# SPD_Programmer.net
KiCad netlist of a schematic drawn in Altium Designer
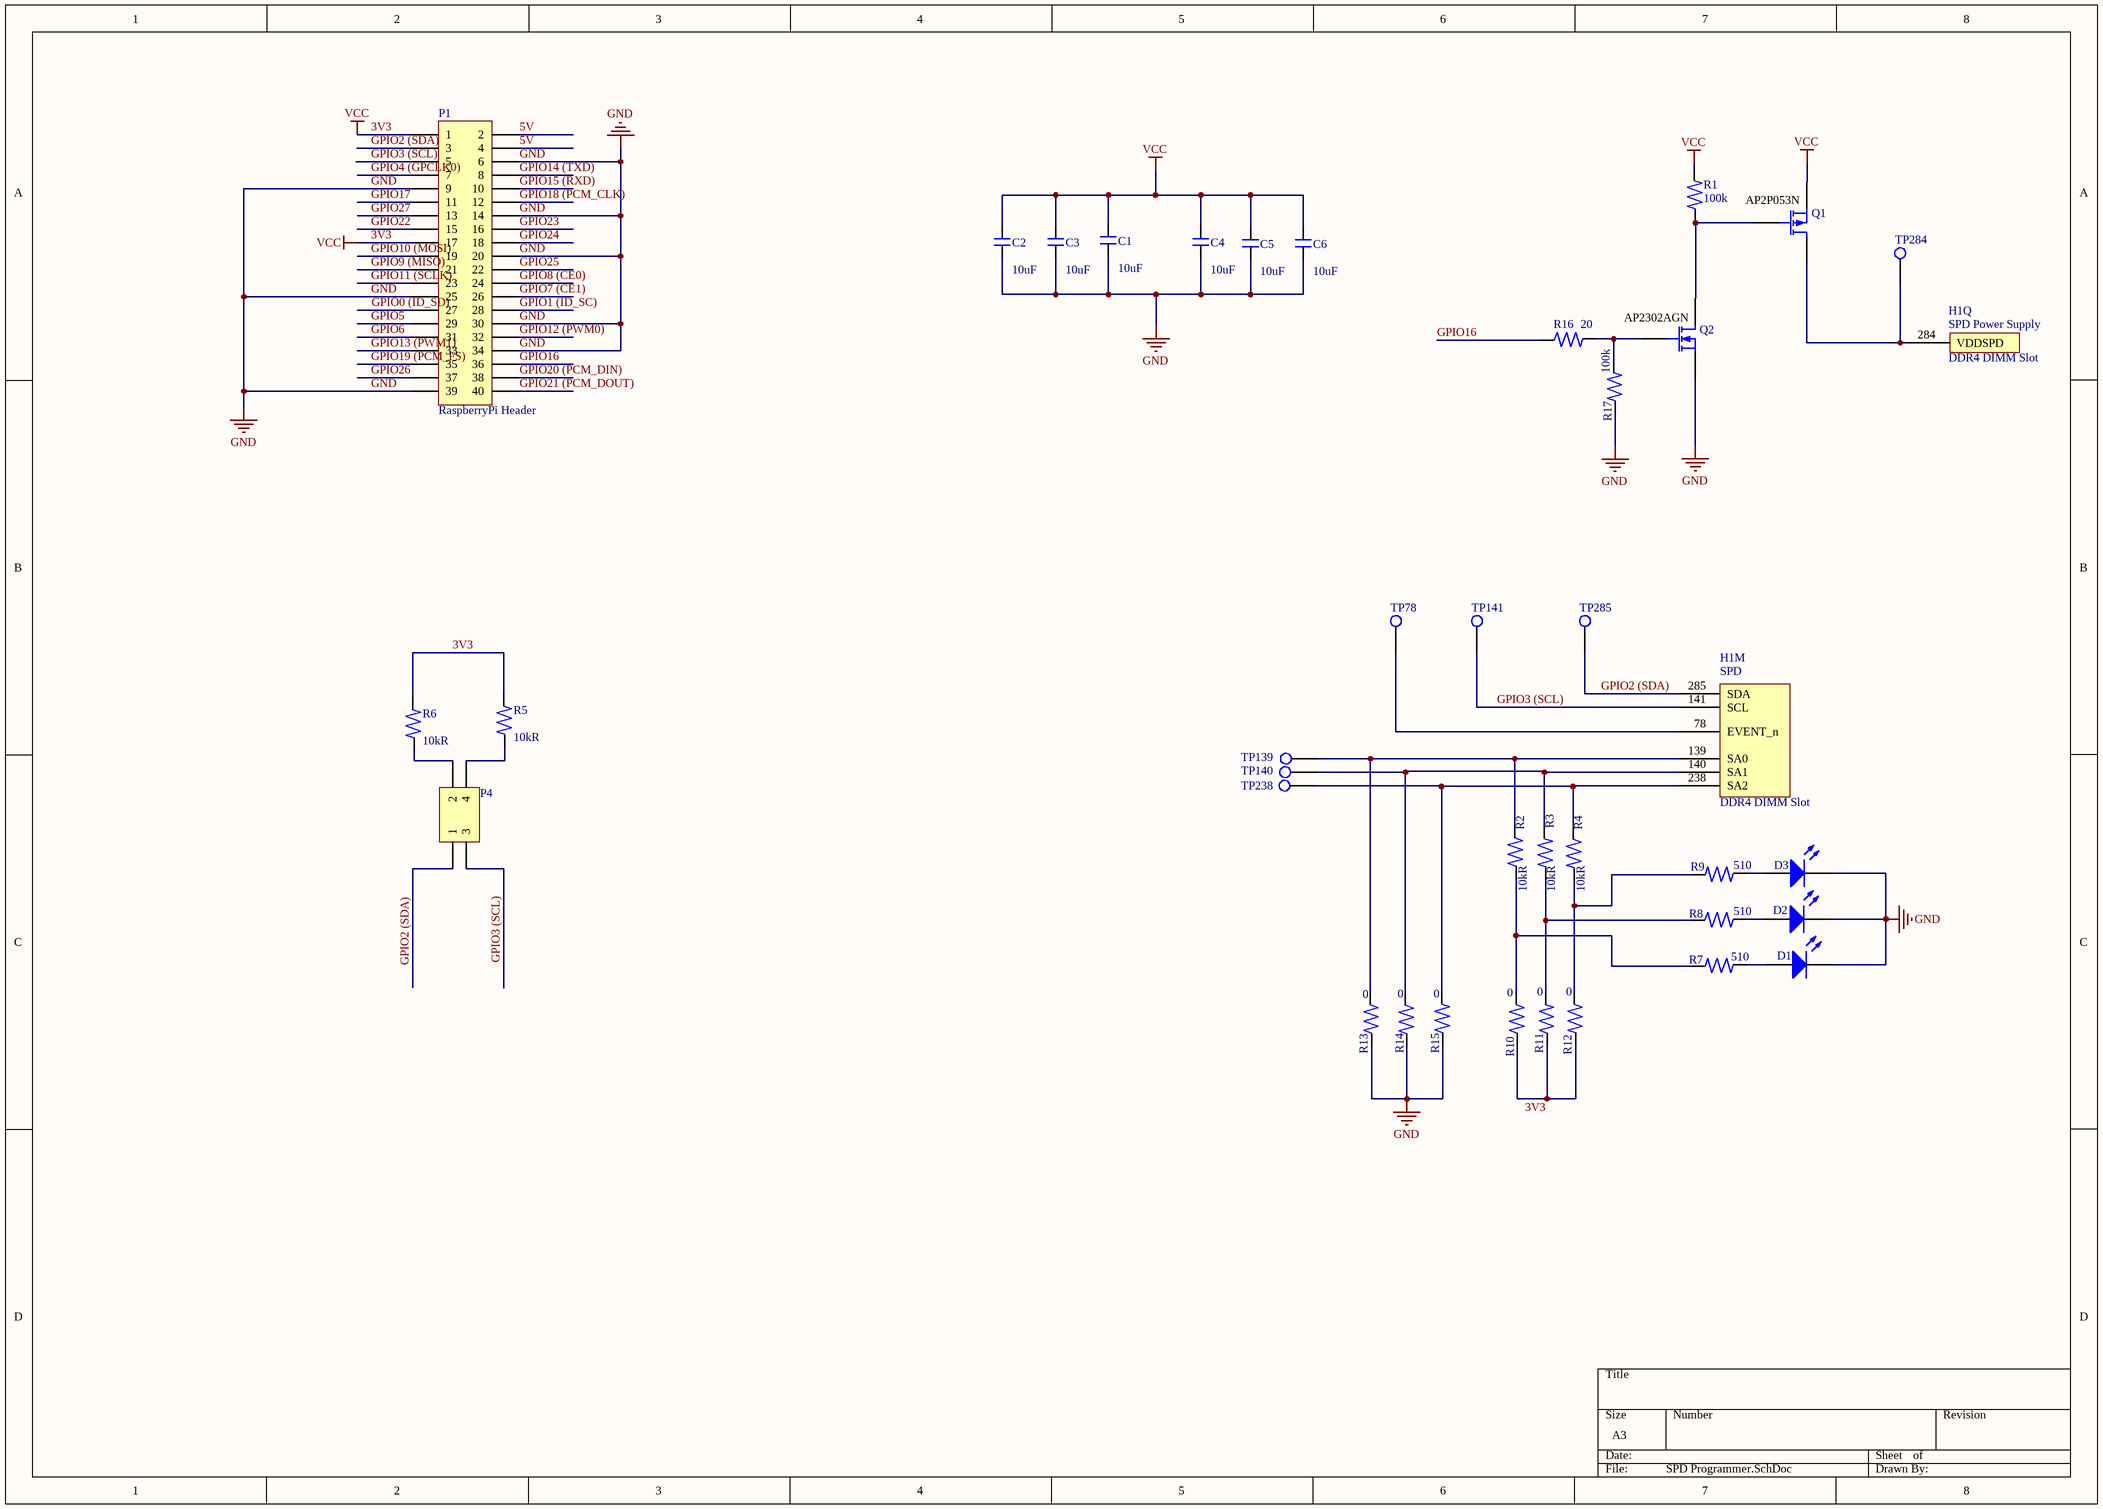
[diagram p0: SPD Programmer.SchDoc]

(export (version "E")
  (design (tool "Eeschema 10.0.6"))
  (components
    (comp (ref "C1")
      (value "Capacitor 0603")
      (footprint "Capacitor 0603")
      (fields
        (field (name "MANUFACTURER") "Vishay")
        (field (name "MANUFACTURER PART NUMBER") "CRCW060310K0FKEA")
        (field (name "TOLERANCE") "1%")
        (field (name "CAPACITANCE") "10uF")
      )
      (libsource (lib "RouterIntLib") (part "Capacitor 0603"))
    )
    (comp (ref "C2")
      (value "Capacitor 0603")
      (footprint "Capacitor 0603")
      (fields
        (field (name "MANUFACTURER") "Vishay")
        (field (name "MANUFACTURER PART NUMBER") "CRCW060310K0FKEA")
        (field (name "TOLERANCE") "1%")
        (field (name "CAPACITANCE") "10uF")
      )
      (libsource (lib "RouterIntLib") (part "Capacitor 0603"))
    )
    (comp (ref "C3")
      (value "Capacitor 0603")
      (footprint "Capacitor 0603")
      (fields
        (field (name "MANUFACTURER") "Vishay")
        (field (name "MANUFACTURER PART NUMBER") "CRCW060310K0FKEA")
        (field (name "TOLERANCE") "1%")
        (field (name "CAPACITANCE") "10uF")
      )
      (libsource (lib "RouterIntLib") (part "Capacitor 0603"))
    )
    (comp (ref "C4")
      (value "Capacitor 0603")
      (footprint "Capacitor 0603")
      (fields
        (field (name "MANUFACTURER") "Vishay")
        (field (name "MANUFACTURER PART NUMBER") "CRCW060310K0FKEA")
        (field (name "TOLERANCE") "1%")
        (field (name "CAPACITANCE") "10uF")
      )
      (libsource (lib "RouterIntLib") (part "Capacitor 0603"))
    )
    (comp (ref "C5")
      (value "Capacitor 0603")
      (footprint "Capacitor 0603")
      (fields
        (field (name "MANUFACTURER") "Vishay")
        (field (name "MANUFACTURER PART NUMBER") "CRCW060310K0FKEA")
        (field (name "TOLERANCE") "1%")
        (field (name "CAPACITANCE") "10uF")
      )
      (libsource (lib "RouterIntLib") (part "Capacitor 0603"))
    )
    (comp (ref "C6")
      (value "Capacitor 0603")
      (footprint "Capacitor 0603")
      (fields
        (field (name "MANUFACTURER") "Vishay")
        (field (name "MANUFACTURER PART NUMBER") "CRCW060310K0FKEA")
        (field (name "TOLERANCE") "1%")
        (field (name "CAPACITANCE") "10uF")
      )
      (libsource (lib "RouterIntLib") (part "Capacitor 0603"))
    )
    (comp (ref "D1")
      (value "LED2")
      (footprint "3.2X1.6X1.1")
      (description "Typical RED, GREEN, YELLOW, AMBER GaAs LED")
      (fields (field (name "PUBLISHER") "Altium Limited"))
      (libsource (lib "Miscellaneous Devices") (part "LED2"))
    )
    (comp (ref "D2")
      (value "LED2")
      (footprint "3.2X1.6X1.1")
      (description "Typical RED, GREEN, YELLOW, AMBER GaAs LED")
      (fields (field (name "PUBLISHER") "Altium Limited"))
      (libsource (lib "Miscellaneous Devices") (part "LED2"))
    )
    (comp (ref "D3")
      (value "LED2")
      (footprint "3.2X1.6X1.1")
      (description "Typical RED, GREEN, YELLOW, AMBER GaAs LED")
      (fields (field (name "PUBLISHER") "Altium Limited"))
      (libsource (lib "Miscellaneous Devices") (part "LED2"))
    )
    (comp (ref "H1")
      (value "DDR4 DIMM Slot")
      (footprint "DDR4 DIMM Slot")
      (libsource (lib "RouterIntLib") (part "DDR4 DIMM Slot"))
    )
    (comp (ref "P1")
      (value "RaspberryPi Header")
      (footprint "HDR2X20")
      (description "Header, 20-Pin, Dual row")
      (fields (field (name "PUBLISHER") "Altium Limited"))
      (libsource (lib "Miscellaneous Connectors") (part "Header 20X2"))
    )
    (comp (ref "P4")
      (value "Header 2X2")
      (footprint "HDR2X2")
      (description "Header, 2-Pin, Dual row")
      (fields (field (name "PUBLISHER") "Altium Limited"))
      (libsource (lib "Miscellaneous Connectors") (part "Header 2X2"))
    )
    (comp (ref "Q1") (value "MOSFET-P") (footprint "SOT23") (libsource (lib "RouterIntLib") (part "PMOS")))
    (comp (ref "Q2")
      (value "MOSFET-N")
      (footprint "SOT23")
      (fields (field (name "PUBLISHER") "Altium Limited"))
      (libsource (lib "RouterIntLib") (part "NMOS"))
    )
    (comp (ref "R1")
      (value "Resistor 0603")
      (footprint "Resistor 0603")
      (fields
        (field (name "MANUFACTURER") "Vishay")
        (field (name "MANUFACTURER PART NUMBER") "CRCW060310K0FKEA")
        (field (name "TOLERANCE") "1%")
        (field (name "RESISTANCE") "100k")
      )
      (libsource (lib "RouterIntLib") (part "Resistor 0603"))
    )
    (comp (ref "R2")
      (value "Resistor 0603")
      (footprint "Resistor 0603")
      (fields
        (field (name "MANUFACTURER") "Vishay")
        (field (name "MANUFACTURER PART NUMBER") "CRCW060310K0FKEA")
        (field (name "TOLERANCE") "1%")
        (field (name "RESISTANCE") "10kR")
      )
      (libsource (lib "RouterIntLib") (part "Resistor 0603"))
    )
    (comp (ref "R3")
      (value "Resistor 0603")
      (footprint "Resistor 0603")
      (fields
        (field (name "MANUFACTURER") "Vishay")
        (field (name "MANUFACTURER PART NUMBER") "CRCW060310K0FKEA")
        (field (name "TOLERANCE") "1%")
        (field (name "RESISTANCE") "10kR")
      )
      (libsource (lib "RouterIntLib") (part "Resistor 0603"))
    )
    (comp (ref "R4")
      (value "Resistor 0603")
      (footprint "Resistor 0603")
      (fields
        (field (name "MANUFACTURER") "Vishay")
        (field (name "MANUFACTURER PART NUMBER") "CRCW060310K0FKEA")
        (field (name "TOLERANCE") "1%")
        (field (name "RESISTANCE") "10kR")
      )
      (libsource (lib "RouterIntLib") (part "Resistor 0603"))
    )
    (comp (ref "R5")
      (value "Resistor 0603")
      (footprint "Resistor 0603")
      (fields
        (field (name "MANUFACTURER") "Vishay")
        (field (name "MANUFACTURER PART NUMBER") "CRCW060310K0FKEA")
        (field (name "TOLERANCE") "1%")
        (field (name "RESISTANCE") "10kR")
      )
      (libsource (lib "RouterIntLib") (part "Resistor 0603"))
    )
    (comp (ref "R6")
      (value "Resistor 0603")
      (footprint "Resistor 0603")
      (fields
        (field (name "MANUFACTURER") "Vishay")
        (field (name "MANUFACTURER PART NUMBER") "CRCW060310K0FKEA")
        (field (name "TOLERANCE") "1%")
        (field (name "RESISTANCE") "10kR")
      )
      (libsource (lib "RouterIntLib") (part "Resistor 0603"))
    )
    (comp (ref "R7")
      (value "Resistor 0603")
      (footprint "Resistor 0603")
      (fields
        (field (name "MANUFACTURER") "Vishay")
        (field (name "MANUFACTURER PART NUMBER") "CRCW060310K0FKEA")
        (field (name "TOLERANCE") "1%")
        (field (name "RESISTANCE") "510")
      )
      (libsource (lib "RouterIntLib") (part "Resistor 0603"))
    )
    (comp (ref "R8")
      (value "Resistor 0603")
      (footprint "Resistor 0603")
      (fields
        (field (name "MANUFACTURER") "Vishay")
        (field (name "MANUFACTURER PART NUMBER") "CRCW060310K0FKEA")
        (field (name "TOLERANCE") "1%")
        (field (name "RESISTANCE") "510")
      )
      (libsource (lib "RouterIntLib") (part "Resistor 0603"))
    )
    (comp (ref "R9")
      (value "Resistor 0603")
      (footprint "Resistor 0603")
      (fields
        (field (name "MANUFACTURER") "Vishay")
        (field (name "MANUFACTURER PART NUMBER") "CRCW060310K0FKEA")
        (field (name "TOLERANCE") "1%")
        (field (name "RESISTANCE") "510")
      )
      (libsource (lib "RouterIntLib") (part "Resistor 0603"))
    )
    (comp (ref "R10")
      (value "Resistor 0603")
      (footprint "Resistor 0603")
      (fields
        (field (name "MANUFACTURER") "Vishay")
        (field (name "MANUFACTURER PART NUMBER") "CRCW060310K0FKEA")
        (field (name "TOLERANCE") "1%")
        (field (name "RESISTANCE") "0")
      )
      (libsource (lib "RouterIntLib") (part "Resistor 0603"))
    )
    (comp (ref "R11")
      (value "Resistor 0603")
      (footprint "Resistor 0603")
      (fields
        (field (name "MANUFACTURER") "Vishay")
        (field (name "MANUFACTURER PART NUMBER") "CRCW060310K0FKEA")
        (field (name "TOLERANCE") "1%")
        (field (name "RESISTANCE") "0")
      )
      (libsource (lib "RouterIntLib") (part "Resistor 0603"))
    )
    (comp (ref "R12")
      (value "Resistor 0603")
      (footprint "Resistor 0603")
      (fields
        (field (name "MANUFACTURER") "Vishay")
        (field (name "MANUFACTURER PART NUMBER") "CRCW060310K0FKEA")
        (field (name "TOLERANCE") "1%")
        (field (name "RESISTANCE") "0")
      )
      (libsource (lib "RouterIntLib") (part "Resistor 0603"))
    )
    (comp (ref "R13")
      (value "Resistor 0603")
      (footprint "Resistor 0603")
      (fields
        (field (name "MANUFACTURER") "Vishay")
        (field (name "MANUFACTURER PART NUMBER") "CRCW060310K0FKEA")
        (field (name "TOLERANCE") "1%")
        (field (name "RESISTANCE") "0")
      )
      (libsource (lib "RouterIntLib") (part "Resistor 0603"))
    )
    (comp (ref "R14")
      (value "Resistor 0603")
      (footprint "Resistor 0603")
      (fields
        (field (name "MANUFACTURER") "Vishay")
        (field (name "MANUFACTURER PART NUMBER") "CRCW060310K0FKEA")
        (field (name "TOLERANCE") "1%")
        (field (name "RESISTANCE") "0")
      )
      (libsource (lib "RouterIntLib") (part "Resistor 0603"))
    )
    (comp (ref "R15")
      (value "Resistor 0603")
      (footprint "Resistor 0603")
      (fields
        (field (name "MANUFACTURER") "Vishay")
        (field (name "MANUFACTURER PART NUMBER") "CRCW060310K0FKEA")
        (field (name "TOLERANCE") "1%")
        (field (name "RESISTANCE") "0")
      )
      (libsource (lib "RouterIntLib") (part "Resistor 0603"))
    )
    (comp (ref "R16")
      (value "Resistor 0603")
      (footprint "Resistor 0603")
      (fields
        (field (name "MANUFACTURER") "Vishay")
        (field (name "MANUFACTURER PART NUMBER") "CRCW060310K0FKEA")
        (field (name "TOLERANCE") "1%")
        (field (name "RESISTANCE") "20")
      )
      (libsource (lib "RouterIntLib") (part "Resistor 0603"))
    )
    (comp (ref "R17")
      (value "Resistor 0603")
      (footprint "Resistor 0603")
      (fields
        (field (name "MANUFACTURER") "Vishay")
        (field (name "MANUFACTURER PART NUMBER") "CRCW060310K0FKEA")
        (field (name "TOLERANCE") "1%")
        (field (name "RESISTANCE") "100k")
      )
      (libsource (lib "RouterIntLib") (part "Resistor 0603"))
    )
    (comp (ref "TP78")
      (value "Test Point")
      (footprint "Test Point")
      (libsource (lib "RouterIntLib") (part "Test Point"))
    )
    (comp (ref "TP139")
      (value "Test Point")
      (footprint "Test Point")
      (libsource (lib "RouterIntLib") (part "Test Point"))
    )
    (comp (ref "TP140")
      (value "Test Point")
      (footprint "Test Point")
      (libsource (lib "RouterIntLib") (part "Test Point"))
    )
    (comp (ref "TP141")
      (value "Test Point")
      (footprint "Test Point")
      (libsource (lib "RouterIntLib") (part "Test Point"))
    )
    (comp (ref "TP238")
      (value "Test Point")
      (footprint "Test Point")
      (libsource (lib "RouterIntLib") (part "Test Point"))
    )
    (comp (ref "TP284")
      (value "Test Point")
      (footprint "Test Point")
      (libsource (lib "RouterIntLib") (part "Test Point"))
    )
    (comp (ref "TP285")
      (value "Test Point")
      (footprint "Test Point")
      (libsource (lib "RouterIntLib") (part "Test Point"))
    )
  )
  (nets
    (net (code "1") (name "/5V") (class "Default")
      (node (ref "P1") (pin "2") (pinfunction "2_2") (pintype "passive"))
      (node (ref "P1") (pin "4") (pinfunction "4_4") (pintype "passive"))
    )
    (net (code "2") (name "/GPIO0 (ID_SD)") (class "Default")
      (node (ref "P1") (pin "27") (pinfunction "27_27") (pintype "passive"))
    )
    (net (code "3") (name "/GPIO1 (ID_SC)") (class "Default")
      (node (ref "P1") (pin "28") (pinfunction "28_28") (pintype "passive"))
    )
    (net (code "4") (name "/GPIO2 (SDA)") (class "Default")
      (node (ref "H1") (pin "285") (pinfunction "SDA_285") (pintype "passive"))
      (node (ref "P1") (pin "3") (pinfunction "3_3") (pintype "passive"))
      (node (ref "P4") (pin "1") (pinfunction "1_1") (pintype "passive"))
      (node (ref "TP285") (pin "1") (pinfunction "1_1") (pintype "passive"))
    )
    (net (code "5") (name "/GPIO3 (SCL)") (class "Default")
      (node (ref "H1") (pin "141") (pinfunction "SCL_141") (pintype "passive"))
      (node (ref "P1") (pin "5") (pinfunction "5_5") (pintype "passive"))
      (node (ref "P4") (pin "3") (pinfunction "3_3") (pintype "passive"))
      (node (ref "TP141") (pin "1") (pinfunction "1_1") (pintype "passive"))
    )
    (net (code "6") (name "/GPIO4 (GPCLK0)") (class "Default")
      (node (ref "P1") (pin "7") (pinfunction "7_7") (pintype "passive"))
    )
    (net (code "7") (name "/GPIO5") (class "Default")
      (node (ref "P1") (pin "29") (pinfunction "29_29") (pintype "passive"))
    )
    (net (code "8") (name "/GPIO6") (class "Default")
      (node (ref "P1") (pin "31") (pinfunction "31_31") (pintype "passive"))
    )
    (net (code "9") (name "/GPIO7 (CE1)") (class "Default")
      (node (ref "P1") (pin "26") (pinfunction "26_26") (pintype "passive"))
    )
    (net (code "10") (name "/GPIO8 (CE0)") (class "Default")
      (node (ref "P1") (pin "24") (pinfunction "24_24") (pintype "passive"))
    )
    (net (code "11") (name "/GPIO9 (MISO)") (class "Default")
      (node (ref "P1") (pin "21") (pinfunction "21_21") (pintype "passive"))
    )
    (net (code "12") (name "/GPIO10 (MOSI)") (class "Default")
      (node (ref "P1") (pin "19") (pinfunction "19_19") (pintype "passive"))
    )
    (net (code "13") (name "/GPIO11 (SCLK)") (class "Default")
      (node (ref "P1") (pin "23") (pinfunction "23_23") (pintype "passive"))
    )
    (net (code "14") (name "/GPIO12 (PWM0)") (class "Default")
      (node (ref "P1") (pin "32") (pinfunction "32_32") (pintype "passive"))
    )
    (net (code "15") (name "/GPIO13 (PWM1)") (class "Default")
      (node (ref "P1") (pin "33") (pinfunction "33_33") (pintype "passive"))
    )
    (net (code "16") (name "/GPIO14 (TXD)") (class "Default")
      (node (ref "P1") (pin "8") (pinfunction "8_8") (pintype "passive"))
    )
    (net (code "17") (name "/GPIO15 (RXD)") (class "Default")
      (node (ref "P1") (pin "10") (pinfunction "10_10") (pintype "passive"))
    )
    (net (code "18") (name "/GPIO16") (class "Default")
      (node (ref "P1") (pin "36") (pinfunction "36_36") (pintype "passive"))
      (node (ref "R16") (pin "1") (pinfunction "1_1") (pintype "passive"))
    )
    (net (code "19") (name "/GPIO17") (class "Default")
      (node (ref "P1") (pin "11") (pinfunction "11_11") (pintype "passive"))
    )
    (net (code "20") (name "/GPIO18 (PCM_CLK)") (class "Default")
      (node (ref "P1") (pin "12") (pinfunction "12_12") (pintype "passive"))
    )
    (net (code "21") (name "/GPIO19 (PCM_FS)") (class "Default")
      (node (ref "P1") (pin "35") (pinfunction "35_35") (pintype "passive"))
    )
    (net (code "22") (name "/GPIO20 (PCM_DIN)") (class "Default")
      (node (ref "P1") (pin "38") (pinfunction "38_38") (pintype "passive"))
    )
    (net (code "23") (name "/GPIO21 (PCM_DOUT)") (class "Default")
      (node (ref "P1") (pin "40") (pinfunction "40_40") (pintype "passive"))
    )
    (net (code "24") (name "/GPIO22") (class "Default")
      (node (ref "P1") (pin "15") (pinfunction "15_15") (pintype "passive"))
    )
    (net (code "25") (name "/GPIO23") (class "Default")
      (node (ref "P1") (pin "16") (pinfunction "16_16") (pintype "passive"))
    )
    (net (code "26") (name "/GPIO24") (class "Default")
      (node (ref "P1") (pin "18") (pinfunction "18_18") (pintype "passive"))
    )
    (net (code "27") (name "/GPIO25") (class "Default")
      (node (ref "P1") (pin "22") (pinfunction "22_22") (pintype "passive"))
    )
    (net (code "28") (name "/GPIO26") (class "Default")
      (node (ref "P1") (pin "37") (pinfunction "37_37") (pintype "passive"))
    )
    (net (code "29") (name "/GPIO27") (class "Default")
      (node (ref "P1") (pin "13") (pinfunction "13_13") (pintype "passive"))
    )
    (net (code "30") (name "GND") (class "Default")
      (node (ref "C1") (pin "1") (pinfunction "1_1") (pintype "passive"))
      (node (ref "C2") (pin "1") (pinfunction "1_1") (pintype "passive"))
      (node (ref "C3") (pin "1") (pinfunction "1_1") (pintype "passive"))
      (node (ref "C4") (pin "1") (pinfunction "1_1") (pintype "passive"))
      (node (ref "C5") (pin "1") (pinfunction "1_1") (pintype "passive"))
      (node (ref "C6") (pin "1") (pinfunction "1_1") (pintype "passive"))
      (node (ref "D1") (pin "2") (pinfunction "K_2") (pintype "passive"))
      (node (ref "D2") (pin "2") (pinfunction "K_2") (pintype "passive"))
      (node (ref "D3") (pin "2") (pinfunction "K_2") (pintype "passive"))
      (node (ref "P1") (pin "14") (pinfunction "14_14") (pintype "passive"))
      (node (ref "P1") (pin "20") (pinfunction "20_20") (pintype "passive"))
      (node (ref "P1") (pin "25") (pinfunction "25_25") (pintype "passive"))
      (node (ref "P1") (pin "30") (pinfunction "30_30") (pintype "passive"))
      (node (ref "P1") (pin "34") (pinfunction "34_34") (pintype "passive"))
      (node (ref "P1") (pin "39") (pinfunction "39_39") (pintype "passive"))
      (node (ref "P1") (pin "6") (pinfunction "6_6") (pintype "passive"))
      (node (ref "P1") (pin "9") (pinfunction "9_9") (pintype "passive"))
      (node (ref "Q2") (pin "2") (pinfunction "S_2") (pintype "passive"))
      (node (ref "R13") (pin "2") (pinfunction "2_2") (pintype "passive"))
      (node (ref "R14") (pin "2") (pinfunction "2_2") (pintype "passive"))
      (node (ref "R15") (pin "2") (pinfunction "2_2") (pintype "passive"))
      (node (ref "R17") (pin "2") (pinfunction "2_2") (pintype "passive"))
    )
    (net (code "31") (name "Net-(D1-A)") (class "Default")
      (node (ref "D1") (pin "1") (pinfunction "A_1") (pintype "passive"))
      (node (ref "R7") (pin "1") (pinfunction "1_1") (pintype "passive"))
    )
    (net (code "32") (name "Net-(D2-A)") (class "Default")
      (node (ref "D2") (pin "1") (pinfunction "A_1") (pintype "passive"))
      (node (ref "R8") (pin "1") (pinfunction "1_1") (pintype "passive"))
    )
    (net (code "33") (name "Net-(D3-A)") (class "Default")
      (node (ref "D3") (pin "1") (pinfunction "A_1") (pintype "passive"))
      (node (ref "R9") (pin "2") (pinfunction "2_2") (pintype "passive"))
    )
    (net (code "34") (name "Net-(H1M-EVENT_n)") (class "Default")
      (node (ref "H1") (pin "78") (pinfunction "EVENT_n_78") (pintype "passive"))
      (node (ref "TP78") (pin "1") (pinfunction "1_1") (pintype "passive"))
    )
    (net (code "35") (name "Net-(H1M-SA0)") (class "Default")
      (node (ref "H1") (pin "139") (pinfunction "SA0_139") (pintype "passive"))
      (node (ref "R13") (pin "1") (pinfunction "1_1") (pintype "passive"))
      (node (ref "R2") (pin "2") (pinfunction "2_2") (pintype "passive"))
      (node (ref "TP139") (pin "1") (pinfunction "1_1") (pintype "passive"))
    )
    (net (code "36") (name "Net-(H1M-SA1)") (class "Default")
      (node (ref "H1") (pin "140") (pinfunction "SA1_140") (pintype "passive"))
      (node (ref "R14") (pin "1") (pinfunction "1_1") (pintype "passive"))
      (node (ref "R3") (pin "2") (pinfunction "2_2") (pintype "passive"))
      (node (ref "TP140") (pin "1") (pinfunction "1_1") (pintype "passive"))
    )
    (net (code "37") (name "Net-(H1M-SA2)") (class "Default")
      (node (ref "H1") (pin "238") (pinfunction "SA2_238") (pintype "passive"))
      (node (ref "R15") (pin "1") (pinfunction "1_1") (pintype "passive"))
      (node (ref "R4") (pin "2") (pinfunction "2_2") (pintype "passive"))
      (node (ref "TP238") (pin "1") (pinfunction "1_1") (pintype "passive"))
    )
    (net (code "38") (name "Net-(H1Q-VDDSPD)") (class "Default")
      (node (ref "H1") (pin "284") (pinfunction "VDDSPD_284") (pintype "passive"))
      (node (ref "Q1") (pin "3") (pinfunction "D_3") (pintype "passive"))
      (node (ref "TP284") (pin "1") (pinfunction "1_1") (pintype "passive"))
    )
    (net (code "39") (name "Net-(P4-Pad2)") (class "Default")
      (node (ref "P4") (pin "2") (pinfunction "2_2") (pintype "passive"))
      (node (ref "R6") (pin "1") (pinfunction "1_1") (pintype "passive"))
    )
    (net (code "40") (name "Net-(P4-Pad4)") (class "Default")
      (node (ref "P4") (pin "4") (pinfunction "4_4") (pintype "passive"))
      (node (ref "R5") (pin "1") (pinfunction "1_1") (pintype "passive"))
    )
    (net (code "41") (name "Net-(Q1-G)") (class "Default")
      (node (ref "Q1") (pin "1") (pinfunction "G_1") (pintype "passive"))
      (node (ref "Q2") (pin "3") (pinfunction "D_3") (pintype "passive"))
      (node (ref "R1") (pin "1") (pinfunction "1_1") (pintype "passive"))
    )
    (net (code "42") (name "Net-(Q2-G)") (class "Default")
      (node (ref "Q2") (pin "1") (pinfunction "G_1") (pintype "passive"))
      (node (ref "R16") (pin "2") (pinfunction "2_2") (pintype "passive"))
      (node (ref "R17") (pin "1") (pinfunction "1_1") (pintype "passive"))
    )
    (net (code "43") (name "Net-(R10-Pad1)") (class "Default")
      (node (ref "R10") (pin "1") (pinfunction "1_1") (pintype "passive"))
      (node (ref "R2") (pin "1") (pinfunction "1_1") (pintype "passive"))
      (node (ref "R7") (pin "2") (pinfunction "2_2") (pintype "passive"))
    )
    (net (code "44") (name "Net-(R11-Pad1)") (class "Default")
      (node (ref "R11") (pin "1") (pinfunction "1_1") (pintype "passive"))
      (node (ref "R3") (pin "1") (pinfunction "1_1") (pintype "passive"))
      (node (ref "R8") (pin "2") (pinfunction "2_2") (pintype "passive"))
    )
    (net (code "45") (name "Net-(R12-Pad1)") (class "Default")
      (node (ref "R12") (pin "1") (pinfunction "1_1") (pintype "passive"))
      (node (ref "R4") (pin "1") (pinfunction "1_1") (pintype "passive"))
      (node (ref "R9") (pin "1") (pinfunction "1_1") (pintype "passive"))
    )
    (net (code "46") (name "VCC") (class "Default")
      (node (ref "C1") (pin "2") (pinfunction "2_2") (pintype "passive"))
      (node (ref "C2") (pin "2") (pinfunction "2_2") (pintype "passive"))
      (node (ref "C3") (pin "2") (pinfunction "2_2") (pintype "passive"))
      (node (ref "C4") (pin "2") (pinfunction "2_2") (pintype "passive"))
      (node (ref "C5") (pin "2") (pinfunction "2_2") (pintype "passive"))
      (node (ref "C6") (pin "2") (pinfunction "2_2") (pintype "passive"))
      (node (ref "P1") (pin "1") (pinfunction "1_1") (pintype "passive"))
      (node (ref "P1") (pin "17") (pinfunction "17_17") (pintype "passive"))
      (node (ref "Q1") (pin "2") (pinfunction "S_2") (pintype "passive"))
      (node (ref "R1") (pin "2") (pinfunction "2_2") (pintype "passive"))
      (node (ref "R10") (pin "2") (pinfunction "2_2") (pintype "passive"))
      (node (ref "R11") (pin "2") (pinfunction "2_2") (pintype "passive"))
      (node (ref "R12") (pin "2") (pinfunction "2_2") (pintype "passive"))
      (node (ref "R5") (pin "2") (pinfunction "2_2") (pintype "passive"))
      (node (ref "R6") (pin "2") (pinfunction "2_2") (pintype "passive"))
    )
  )
)
